# Ports.net
KiCad netlist of a schematic drawn in Altium Designer
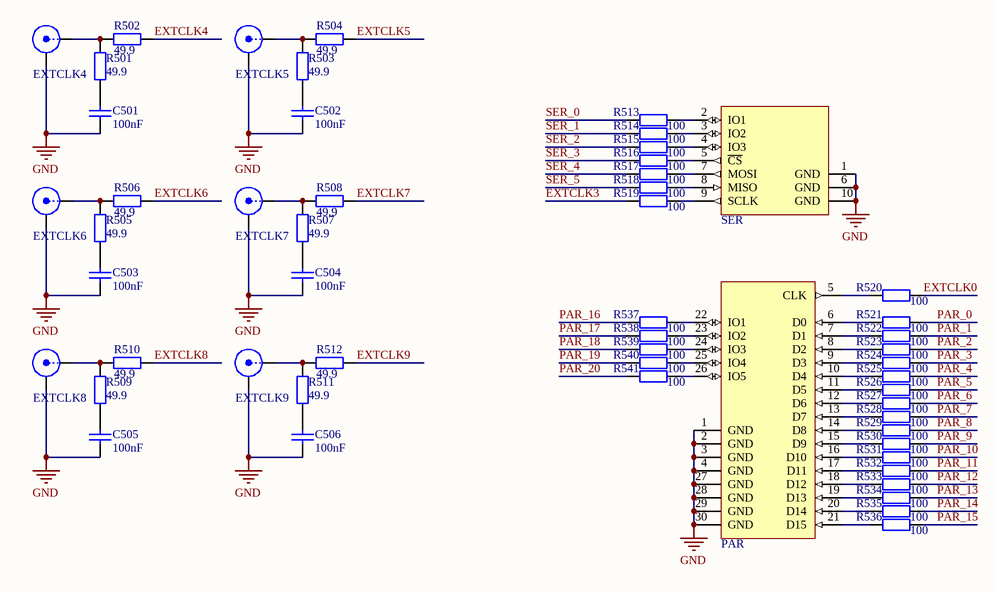
[diagram p0: Ports.SchDoc]

(export (version "E")
  (design (tool "Eeschema 10.0.6"))
  (components
    (comp (ref "C501")
      (value "100nF")
      (footprint "0603C")
      (description "MLCC")
      (libsource (lib "Misc") (part "MLCC"))
    )
    (comp (ref "C502")
      (value "100nF")
      (footprint "0603C")
      (description "MLCC")
      (libsource (lib "Misc") (part "MLCC"))
    )
    (comp (ref "C503")
      (value "100nF")
      (footprint "0603C")
      (description "MLCC")
      (libsource (lib "Misc") (part "MLCC"))
    )
    (comp (ref "C504")
      (value "100nF")
      (footprint "0603C")
      (description "MLCC")
      (libsource (lib "Misc") (part "MLCC"))
    )
    (comp (ref "C505")
      (value "100nF")
      (footprint "0603C")
      (description "MLCC")
      (libsource (lib "Misc") (part "MLCC"))
    )
    (comp (ref "C506")
      (value "100nF")
      (footprint "0603C")
      (description "MLCC")
      (libsource (lib "Misc") (part "MLCC"))
    )
    (comp (ref "EXTCLK4")
      (value "SMA")
      (footprint "SMA-V-NARROW")
      (description "SMA Connector")
      (libsource (lib "SMA") (part "SMA"))
    )
    (comp (ref "EXTCLK5")
      (value "SMA")
      (footprint "SMA-V-NARROW")
      (description "SMA Connector")
      (libsource (lib "SMA") (part "SMA"))
    )
    (comp (ref "EXTCLK6")
      (value "SMA")
      (footprint "SMA-V-NARROW")
      (description "SMA Connector")
      (libsource (lib "SMA") (part "SMA"))
    )
    (comp (ref "EXTCLK7")
      (value "SMA")
      (footprint "SMA-V-NARROW")
      (description "SMA Connector")
      (libsource (lib "SMA") (part "SMA"))
    )
    (comp (ref "EXTCLK8")
      (value "SMA")
      (footprint "SMA-V-NARROW")
      (description "SMA Connector")
      (libsource (lib "SMA") (part "SMA"))
    )
    (comp (ref "EXTCLK9")
      (value "SMA")
      (footprint "SMA-V-NARROW")
      (description "SMA Connector")
      (libsource (lib "SMA") (part "SMA"))
    )
    (comp (ref "PAR")
      (value "FPGA_PAR_SLAVE")
      (footprint "IDC30")
      (description "FPGA parallel port")
      (libsource (lib "Modules") (part "FPGA_PAR_SLAVE"))
    )
    (comp (ref "R501")
      (value "49.9")
      (footprint "0603R")
      (description "Resistor")
      (libsource (lib "") (part "Resistor_1"))
    )
    (comp (ref "R502")
      (value "49.9")
      (footprint "0603R")
      (description "Resistor")
      (libsource (lib "Misc") (part "Resistor"))
    )
    (comp (ref "R503")
      (value "49.9")
      (footprint "0603R")
      (description "Resistor")
      (libsource (lib "") (part "Resistor_1"))
    )
    (comp (ref "R504")
      (value "49.9")
      (footprint "0603R")
      (description "Resistor")
      (libsource (lib "Misc") (part "Resistor"))
    )
    (comp (ref "R505")
      (value "49.9")
      (footprint "0603R")
      (description "Resistor")
      (libsource (lib "") (part "Resistor_1"))
    )
    (comp (ref "R506")
      (value "49.9")
      (footprint "0603R")
      (description "Resistor")
      (libsource (lib "Misc") (part "Resistor"))
    )
    (comp (ref "R507")
      (value "49.9")
      (footprint "0603R")
      (description "Resistor")
      (libsource (lib "") (part "Resistor_1"))
    )
    (comp (ref "R508")
      (value "49.9")
      (footprint "0603R")
      (description "Resistor")
      (libsource (lib "Misc") (part "Resistor"))
    )
    (comp (ref "R509")
      (value "49.9")
      (footprint "0603R")
      (description "Resistor")
      (libsource (lib "") (part "Resistor_1"))
    )
    (comp (ref "R510")
      (value "49.9")
      (footprint "0603R")
      (description "Resistor")
      (libsource (lib "Misc") (part "Resistor"))
    )
    (comp (ref "R511")
      (value "49.9")
      (footprint "0603R")
      (description "Resistor")
      (libsource (lib "") (part "Resistor_1"))
    )
    (comp (ref "R512")
      (value "49.9")
      (footprint "0603R")
      (description "Resistor")
      (libsource (lib "Misc") (part "Resistor"))
    )
    (comp (ref "R513")
      (value "100")
      (footprint "0603R")
      (description "Resistor")
      (libsource (lib "Misc") (part "Resistor"))
    )
    (comp (ref "R514")
      (value "100")
      (footprint "0603R")
      (description "Resistor")
      (libsource (lib "Misc") (part "Resistor"))
    )
    (comp (ref "R515")
      (value "100")
      (footprint "0603R")
      (description "Resistor")
      (libsource (lib "Misc") (part "Resistor"))
    )
    (comp (ref "R516")
      (value "100")
      (footprint "0603R")
      (description "Resistor")
      (libsource (lib "Misc") (part "Resistor"))
    )
    (comp (ref "R517")
      (value "100")
      (footprint "0603R")
      (description "Resistor")
      (libsource (lib "Misc") (part "Resistor"))
    )
    (comp (ref "R518")
      (value "100")
      (footprint "0603R")
      (description "Resistor")
      (libsource (lib "Misc") (part "Resistor"))
    )
    (comp (ref "R519")
      (value "100")
      (footprint "0603R")
      (description "Resistor")
      (libsource (lib "Misc") (part "Resistor"))
    )
    (comp (ref "R520")
      (value "100")
      (footprint "0603R")
      (description "Resistor")
      (libsource (lib "Misc") (part "Resistor"))
    )
    (comp (ref "R521")
      (value "100")
      (footprint "0603R")
      (description "Resistor")
      (libsource (lib "Misc") (part "Resistor"))
    )
    (comp (ref "R522")
      (value "100")
      (footprint "0603R")
      (description "Resistor")
      (libsource (lib "Misc") (part "Resistor"))
    )
    (comp (ref "R523")
      (value "100")
      (footprint "0603R")
      (description "Resistor")
      (libsource (lib "Misc") (part "Resistor"))
    )
    (comp (ref "R524")
      (value "100")
      (footprint "0603R")
      (description "Resistor")
      (libsource (lib "Misc") (part "Resistor"))
    )
    (comp (ref "R525")
      (value "100")
      (footprint "0603R")
      (description "Resistor")
      (libsource (lib "Misc") (part "Resistor"))
    )
    (comp (ref "R526")
      (value "100")
      (footprint "0603R")
      (description "Resistor")
      (libsource (lib "Misc") (part "Resistor"))
    )
    (comp (ref "R527")
      (value "100")
      (footprint "0603R")
      (description "Resistor")
      (libsource (lib "Misc") (part "Resistor"))
    )
    (comp (ref "R528")
      (value "100")
      (footprint "0603R")
      (description "Resistor")
      (libsource (lib "Misc") (part "Resistor"))
    )
    (comp (ref "R529")
      (value "100")
      (footprint "0603R")
      (description "Resistor")
      (libsource (lib "Misc") (part "Resistor"))
    )
    (comp (ref "R530")
      (value "100")
      (footprint "0603R")
      (description "Resistor")
      (libsource (lib "Misc") (part "Resistor"))
    )
    (comp (ref "R531")
      (value "100")
      (footprint "0603R")
      (description "Resistor")
      (libsource (lib "Misc") (part "Resistor"))
    )
    (comp (ref "R532")
      (value "100")
      (footprint "0603R")
      (description "Resistor")
      (libsource (lib "Misc") (part "Resistor"))
    )
    (comp (ref "R533")
      (value "100")
      (footprint "0603R")
      (description "Resistor")
      (libsource (lib "Misc") (part "Resistor"))
    )
    (comp (ref "R534")
      (value "100")
      (footprint "0603R")
      (description "Resistor")
      (libsource (lib "Misc") (part "Resistor"))
    )
    (comp (ref "R535")
      (value "100")
      (footprint "0603R")
      (description "Resistor")
      (libsource (lib "Misc") (part "Resistor"))
    )
    (comp (ref "R536")
      (value "100")
      (footprint "0603R")
      (description "Resistor")
      (libsource (lib "Misc") (part "Resistor"))
    )
    (comp (ref "R537")
      (value "100")
      (footprint "0603R")
      (description "Resistor")
      (libsource (lib "Misc") (part "Resistor"))
    )
    (comp (ref "R538")
      (value "100")
      (footprint "0603R")
      (description "Resistor")
      (libsource (lib "Misc") (part "Resistor"))
    )
    (comp (ref "R539")
      (value "100")
      (footprint "0603R")
      (description "Resistor")
      (libsource (lib "Misc") (part "Resistor"))
    )
    (comp (ref "R540")
      (value "100")
      (footprint "0603R")
      (description "Resistor")
      (libsource (lib "Misc") (part "Resistor"))
    )
    (comp (ref "R541")
      (value "100")
      (footprint "0603R")
      (description "Resistor")
      (libsource (lib "Misc") (part "Resistor"))
    )
    (comp (ref "SER")
      (value "FPGA_SER_SLAVE")
      (footprint "IDC10")
      (description "FPGA serial port")
      (libsource (lib "Modules") (part "FPGA_SER_SLAVE"))
    )
  )
  (nets
    (net (code "1") (name "/EXTCLK0") (class "Default")
      (node (ref "R520") (pin "2") (pinfunction "2_2") (pintype "passive"))
    )
    (net (code "2") (name "/EXTCLK3") (class "Default")
      (node (ref "R519") (pin "1") (pinfunction "1_1") (pintype "passive"))
    )
    (net (code "3") (name "/EXTCLK4") (class "Default")
      (node (ref "R502") (pin "2") (pinfunction "2_2") (pintype "passive"))
    )
    (net (code "4") (name "/EXTCLK5") (class "Default")
      (node (ref "R504") (pin "2") (pinfunction "2_2") (pintype "passive"))
    )
    (net (code "5") (name "/EXTCLK6") (class "Default")
      (node (ref "R506") (pin "2") (pinfunction "2_2") (pintype "passive"))
    )
    (net (code "6") (name "/EXTCLK7") (class "Default")
      (node (ref "R508") (pin "2") (pinfunction "2_2") (pintype "passive"))
    )
    (net (code "7") (name "/EXTCLK8") (class "Default")
      (node (ref "R510") (pin "2") (pinfunction "2_2") (pintype "passive"))
    )
    (net (code "8") (name "/EXTCLK9") (class "Default")
      (node (ref "R512") (pin "2") (pinfunction "2_2") (pintype "passive"))
    )
    (net (code "9") (name "/PAR_0") (class "Default")
      (node (ref "R521") (pin "2") (pinfunction "2_2") (pintype "passive"))
    )
    (net (code "10") (name "/PAR_1") (class "Default")
      (node (ref "R522") (pin "2") (pinfunction "2_2") (pintype "passive"))
    )
    (net (code "11") (name "/PAR_2") (class "Default")
      (node (ref "R523") (pin "2") (pinfunction "2_2") (pintype "passive"))
    )
    (net (code "12") (name "/PAR_3") (class "Default")
      (node (ref "R524") (pin "2") (pinfunction "2_2") (pintype "passive"))
    )
    (net (code "13") (name "/PAR_4") (class "Default")
      (node (ref "R525") (pin "2") (pinfunction "2_2") (pintype "passive"))
    )
    (net (code "14") (name "/PAR_5") (class "Default")
      (node (ref "R526") (pin "2") (pinfunction "2_2") (pintype "passive"))
    )
    (net (code "15") (name "/PAR_6") (class "Default")
      (node (ref "R527") (pin "2") (pinfunction "2_2") (pintype "passive"))
    )
    (net (code "16") (name "/PAR_7") (class "Default")
      (node (ref "R528") (pin "2") (pinfunction "2_2") (pintype "passive"))
    )
    (net (code "17") (name "/PAR_8") (class "Default")
      (node (ref "R529") (pin "2") (pinfunction "2_2") (pintype "passive"))
    )
    (net (code "18") (name "/PAR_9") (class "Default")
      (node (ref "R530") (pin "2") (pinfunction "2_2") (pintype "passive"))
    )
    (net (code "19") (name "/PAR_10") (class "Default")
      (node (ref "R531") (pin "2") (pinfunction "2_2") (pintype "passive"))
    )
    (net (code "20") (name "/PAR_11") (class "Default")
      (node (ref "R532") (pin "2") (pinfunction "2_2") (pintype "passive"))
    )
    (net (code "21") (name "/PAR_12") (class "Default")
      (node (ref "R533") (pin "2") (pinfunction "2_2") (pintype "passive"))
    )
    (net (code "22") (name "/PAR_13") (class "Default")
      (node (ref "R534") (pin "2") (pinfunction "2_2") (pintype "passive"))
    )
    (net (code "23") (name "/PAR_14") (class "Default")
      (node (ref "R535") (pin "2") (pinfunction "2_2") (pintype "passive"))
    )
    (net (code "24") (name "/PAR_15") (class "Default")
      (node (ref "R536") (pin "2") (pinfunction "2_2") (pintype "passive"))
    )
    (net (code "25") (name "/PAR_16") (class "Default")
      (node (ref "R537") (pin "1") (pinfunction "1_1") (pintype "passive"))
    )
    (net (code "26") (name "/PAR_17") (class "Default")
      (node (ref "R538") (pin "1") (pinfunction "1_1") (pintype "passive"))
    )
    (net (code "27") (name "/PAR_18") (class "Default")
      (node (ref "R539") (pin "1") (pinfunction "1_1") (pintype "passive"))
    )
    (net (code "28") (name "/PAR_19") (class "Default")
      (node (ref "R540") (pin "1") (pinfunction "1_1") (pintype "passive"))
    )
    (net (code "29") (name "/PAR_20") (class "Default")
      (node (ref "R541") (pin "1") (pinfunction "1_1") (pintype "passive"))
    )
    (net (code "30") (name "/SER_0") (class "Default")
      (node (ref "R513") (pin "1") (pinfunction "1_1") (pintype "passive"))
    )
    (net (code "31") (name "/SER_1") (class "Default")
      (node (ref "R514") (pin "1") (pinfunction "1_1") (pintype "passive"))
    )
    (net (code "32") (name "/SER_2") (class "Default")
      (node (ref "R515") (pin "1") (pinfunction "1_1") (pintype "passive"))
    )
    (net (code "33") (name "/SER_3") (class "Default")
      (node (ref "R516") (pin "1") (pinfunction "1_1") (pintype "passive"))
    )
    (net (code "34") (name "/SER_4") (class "Default")
      (node (ref "R517") (pin "1") (pinfunction "1_1") (pintype "passive"))
    )
    (net (code "35") (name "/SER_5") (class "Default")
      (node (ref "R518") (pin "1") (pinfunction "1_1") (pintype "passive"))
    )
    (net (code "36") (name "GND") (class "Default")
      (node (ref "C501") (pin "1") (pinfunction "1_1") (pintype "passive"))
      (node (ref "C502") (pin "1") (pinfunction "1_1") (pintype "passive"))
      (node (ref "C503") (pin "1") (pinfunction "1_1") (pintype "passive"))
      (node (ref "C504") (pin "1") (pinfunction "1_1") (pintype "passive"))
      (node (ref "C505") (pin "1") (pinfunction "1_1") (pintype "passive"))
      (node (ref "C506") (pin "1") (pinfunction "1_1") (pintype "passive"))
      (node (ref "EXTCLK4") (pin "2") (pinfunction "Y_2") (pintype "passive"))
      (node (ref "EXTCLK5") (pin "2") (pinfunction "Y_2") (pintype "passive"))
      (node (ref "EXTCLK6") (pin "2") (pinfunction "Y_2") (pintype "passive"))
      (node (ref "EXTCLK7") (pin "2") (pinfunction "Y_2") (pintype "passive"))
      (node (ref "EXTCLK8") (pin "2") (pinfunction "Y_2") (pintype "passive"))
      (node (ref "EXTCLK9") (pin "2") (pinfunction "Y_2") (pintype "passive"))
      (node (ref "PAR") (pin "1") (pinfunction "GND_1") (pintype "power_in"))
      (node (ref "PAR") (pin "2") (pinfunction "GND_2") (pintype "power_in"))
      (node (ref "PAR") (pin "27") (pinfunction "GND_27") (pintype "power_in"))
      (node (ref "PAR") (pin "28") (pinfunction "GND_28") (pintype "power_in"))
      (node (ref "PAR") (pin "29") (pinfunction "GND_29") (pintype "power_in"))
      (node (ref "PAR") (pin "3") (pinfunction "GND_3") (pintype "power_in"))
      (node (ref "PAR") (pin "30") (pinfunction "GND_30") (pintype "power_in"))
      (node (ref "PAR") (pin "4") (pinfunction "GND_4") (pintype "power_in"))
      (node (ref "SER") (pin "1") (pinfunction "GND_1") (pintype "power_in"))
      (node (ref "SER") (pin "10") (pinfunction "GND_10") (pintype "power_in"))
      (node (ref "SER") (pin "6") (pinfunction "GND_6") (pintype "power_in"))
    )
    (net (code "37") (name "Net-(C501-Pad2)") (class "Default")
      (node (ref "C501") (pin "2") (pinfunction "2_2") (pintype "passive"))
      (node (ref "R501") (pin "1") (pinfunction "1_1") (pintype "passive"))
    )
    (net (code "38") (name "Net-(C502-Pad2)") (class "Default")
      (node (ref "C502") (pin "2") (pinfunction "2_2") (pintype "passive"))
      (node (ref "R503") (pin "1") (pinfunction "1_1") (pintype "passive"))
    )
    (net (code "39") (name "Net-(C503-Pad2)") (class "Default")
      (node (ref "C503") (pin "2") (pinfunction "2_2") (pintype "passive"))
      (node (ref "R505") (pin "1") (pinfunction "1_1") (pintype "passive"))
    )
    (net (code "40") (name "Net-(C504-Pad2)") (class "Default")
      (node (ref "C504") (pin "2") (pinfunction "2_2") (pintype "passive"))
      (node (ref "R507") (pin "1") (pinfunction "1_1") (pintype "passive"))
    )
    (net (code "41") (name "Net-(C505-Pad2)") (class "Default")
      (node (ref "C505") (pin "2") (pinfunction "2_2") (pintype "passive"))
      (node (ref "R509") (pin "1") (pinfunction "1_1") (pintype "passive"))
    )
    (net (code "42") (name "Net-(C506-Pad2)") (class "Default")
      (node (ref "C506") (pin "2") (pinfunction "2_2") (pintype "passive"))
      (node (ref "R511") (pin "1") (pinfunction "1_1") (pintype "passive"))
    )
    (net (code "43") (name "Net-(EXTCLK4-X)") (class "Default")
      (node (ref "EXTCLK4") (pin "1") (pinfunction "X_1") (pintype "passive"))
      (node (ref "R501") (pin "2") (pinfunction "2_2") (pintype "passive"))
      (node (ref "R502") (pin "1") (pinfunction "1_1") (pintype "passive"))
    )
    (net (code "44") (name "Net-(EXTCLK5-X)") (class "Default")
      (node (ref "EXTCLK5") (pin "1") (pinfunction "X_1") (pintype "passive"))
      (node (ref "R503") (pin "2") (pinfunction "2_2") (pintype "passive"))
      (node (ref "R504") (pin "1") (pinfunction "1_1") (pintype "passive"))
    )
    (net (code "45") (name "Net-(EXTCLK6-X)") (class "Default")
      (node (ref "EXTCLK6") (pin "1") (pinfunction "X_1") (pintype "passive"))
      (node (ref "R505") (pin "2") (pinfunction "2_2") (pintype "passive"))
      (node (ref "R506") (pin "1") (pinfunction "1_1") (pintype "passive"))
    )
    (net (code "46") (name "Net-(EXTCLK7-X)") (class "Default")
      (node (ref "EXTCLK7") (pin "1") (pinfunction "X_1") (pintype "passive"))
      (node (ref "R507") (pin "2") (pinfunction "2_2") (pintype "passive"))
      (node (ref "R508") (pin "1") (pinfunction "1_1") (pintype "passive"))
    )
    (net (code "47") (name "Net-(EXTCLK8-X)") (class "Default")
      (node (ref "EXTCLK8") (pin "1") (pinfunction "X_1") (pintype "passive"))
      (node (ref "R509") (pin "2") (pinfunction "2_2") (pintype "passive"))
      (node (ref "R510") (pin "1") (pinfunction "1_1") (pintype "passive"))
    )
    (net (code "48") (name "Net-(EXTCLK9-X)") (class "Default")
      (node (ref "EXTCLK9") (pin "1") (pinfunction "X_1") (pintype "passive"))
      (node (ref "R511") (pin "2") (pinfunction "2_2") (pintype "passive"))
      (node (ref "R512") (pin "1") (pinfunction "1_1") (pintype "passive"))
    )
    (net (code "49") (name "Net-(PAR-CLK)") (class "Default")
      (node (ref "PAR") (pin "5") (pinfunction "CLK_5") (pintype "output"))
      (node (ref "R520") (pin "1") (pinfunction "1_1") (pintype "passive"))
    )
    (net (code "50") (name "Net-(PAR-D0)") (class "Default")
      (node (ref "PAR") (pin "6") (pinfunction "D0_6") (pintype "input"))
      (node (ref "R521") (pin "1") (pinfunction "1_1") (pintype "passive"))
    )
    (net (code "51") (name "Net-(PAR-D1)") (class "Default")
      (node (ref "PAR") (pin "7") (pinfunction "D1_7") (pintype "input"))
      (node (ref "R522") (pin "1") (pinfunction "1_1") (pintype "passive"))
    )
    (net (code "52") (name "Net-(PAR-D2)") (class "Default")
      (node (ref "PAR") (pin "8") (pinfunction "D2_8") (pintype "input"))
      (node (ref "R523") (pin "1") (pinfunction "1_1") (pintype "passive"))
    )
    (net (code "53") (name "Net-(PAR-D3)") (class "Default")
      (node (ref "PAR") (pin "9") (pinfunction "D3_9") (pintype "input"))
      (node (ref "R524") (pin "1") (pinfunction "1_1") (pintype "passive"))
    )
    (net (code "54") (name "Net-(PAR-D4)") (class "Default")
      (node (ref "PAR") (pin "10") (pinfunction "D4_10") (pintype "input"))
      (node (ref "R525") (pin "1") (pinfunction "1_1") (pintype "passive"))
    )
    (net (code "55") (name "Net-(PAR-D5)") (class "Default")
      (node (ref "PAR") (pin "11") (pinfunction "D5_11") (pintype "input"))
      (node (ref "R526") (pin "1") (pinfunction "1_1") (pintype "passive"))
    )
    (net (code "56") (name "Net-(PAR-D6)") (class "Default")
      (node (ref "PAR") (pin "12") (pinfunction "D6_12") (pintype "input"))
      (node (ref "R527") (pin "1") (pinfunction "1_1") (pintype "passive"))
    )
    (net (code "57") (name "Net-(PAR-D7)") (class "Default")
      (node (ref "PAR") (pin "13") (pinfunction "D7_13") (pintype "input"))
      (node (ref "R528") (pin "1") (pinfunction "1_1") (pintype "passive"))
    )
    (net (code "58") (name "Net-(PAR-D8)") (class "Default")
      (node (ref "PAR") (pin "14") (pinfunction "D8_14") (pintype "input"))
      (node (ref "R529") (pin "1") (pinfunction "1_1") (pintype "passive"))
    )
    (net (code "59") (name "Net-(PAR-D9)") (class "Default")
      (node (ref "PAR") (pin "15") (pinfunction "D9_15") (pintype "input"))
      (node (ref "R530") (pin "1") (pinfunction "1_1") (pintype "passive"))
    )
    (net (code "60") (name "Net-(PAR-D10)") (class "Default")
      (node (ref "PAR") (pin "16") (pinfunction "D10_16") (pintype "input"))
      (node (ref "R531") (pin "1") (pinfunction "1_1") (pintype "passive"))
    )
    (net (code "61") (name "Net-(PAR-D11)") (class "Default")
      (node (ref "PAR") (pin "17") (pinfunction "D11_17") (pintype "input"))
      (node (ref "R532") (pin "1") (pinfunction "1_1") (pintype "passive"))
    )
    (net (code "62") (name "Net-(PAR-D12)") (class "Default")
      (node (ref "PAR") (pin "18") (pinfunction "D12_18") (pintype "input"))
      (node (ref "R533") (pin "1") (pinfunction "1_1") (pintype "passive"))
    )
    (net (code "63") (name "Net-(PAR-D13)") (class "Default")
      (node (ref "PAR") (pin "19") (pinfunction "D13_19") (pintype "input"))
      (node (ref "R534") (pin "1") (pinfunction "1_1") (pintype "passive"))
    )
    (net (code "64") (name "Net-(PAR-D14)") (class "Default")
      (node (ref "PAR") (pin "20") (pinfunction "D14_20") (pintype "input"))
      (node (ref "R535") (pin "1") (pinfunction "1_1") (pintype "passive"))
    )
    (net (code "65") (name "Net-(PAR-D15)") (class "Default")
      (node (ref "PAR") (pin "21") (pinfunction "D15_21") (pintype "input"))
      (node (ref "R536") (pin "1") (pinfunction "1_1") (pintype "passive"))
    )
    (net (code "66") (name "Net-(PAR-IO1)") (class "Default")
      (node (ref "PAR") (pin "22") (pinfunction "IO1_22") (pintype "bidirectional"))
      (node (ref "R537") (pin "2") (pinfunction "2_2") (pintype "passive"))
    )
    (net (code "67") (name "Net-(PAR-IO2)") (class "Default")
      (node (ref "PAR") (pin "23") (pinfunction "IO2_23") (pintype "bidirectional"))
      (node (ref "R538") (pin "2") (pinfunction "2_2") (pintype "passive"))
    )
    (net (code "68") (name "Net-(PAR-IO3)") (class "Default")
      (node (ref "PAR") (pin "24") (pinfunction "IO3_24") (pintype "bidirectional"))
      (node (ref "R539") (pin "2") (pinfunction "2_2") (pintype "passive"))
    )
    (net (code "69") (name "Net-(PAR-IO4)") (class "Default")
      (node (ref "PAR") (pin "25") (pinfunction "IO4_25") (pintype "bidirectional"))
      (node (ref "R540") (pin "2") (pinfunction "2_2") (pintype "passive"))
    )
    (net (code "70") (name "Net-(PAR-IO5)") (class "Default")
      (node (ref "PAR") (pin "26") (pinfunction "IO5_26") (pintype "bidirectional"))
      (node (ref "R541") (pin "2") (pinfunction "2_2") (pintype "passive"))
    )
    (net (code "71") (name "Net-(SER-IO1)") (class "Default")
      (node (ref "R513") (pin "2") (pinfunction "2_2") (pintype "passive"))
      (node (ref "SER") (pin "2") (pinfunction "IO1_2") (pintype "bidirectional"))
    )
    (net (code "72") (name "Net-(SER-IO2)") (class "Default")
      (node (ref "R514") (pin "2") (pinfunction "2_2") (pintype "passive"))
      (node (ref "SER") (pin "3") (pinfunction "IO2_3") (pintype "bidirectional"))
    )
    (net (code "73") (name "Net-(SER-IO3)") (class "Default")
      (node (ref "R515") (pin "2") (pinfunction "2_2") (pintype "passive"))
      (node (ref "SER") (pin "4") (pinfunction "IO3_4") (pintype "bidirectional"))
    )
    (net (code "74") (name "Net-(SER-MISO)") (class "Default")
      (node (ref "R518") (pin "2") (pinfunction "2_2") (pintype "passive"))
      (node (ref "SER") (pin "8") (pinfunction "MISO_8") (pintype "input"))
    )
    (net (code "75") (name "Net-(SER-MOSI)") (class "Default")
      (node (ref "R517") (pin "2") (pinfunction "2_2") (pintype "passive"))
      (node (ref "SER") (pin "7") (pinfunction "MOSI_7") (pintype "output"))
    )
    (net (code "76") (name "Net-(SER-SCLK)") (class "Default")
      (node (ref "R519") (pin "2") (pinfunction "2_2") (pintype "passive"))
      (node (ref "SER") (pin "9") (pinfunction "SCLK_9") (pintype "output"))
    )
    (net (code "77") (name "Net-(SER-~{CS})") (class "Default")
      (node (ref "R516") (pin "2") (pinfunction "2_2") (pintype "passive"))
      (node (ref "SER") (pin "5") (pinfunction "~{CS}_5") (pintype "output"))
    )
  )
)
